# TEMPLATE_Circuit.net
KiCad netlist of a schematic drawn in Altium Designer
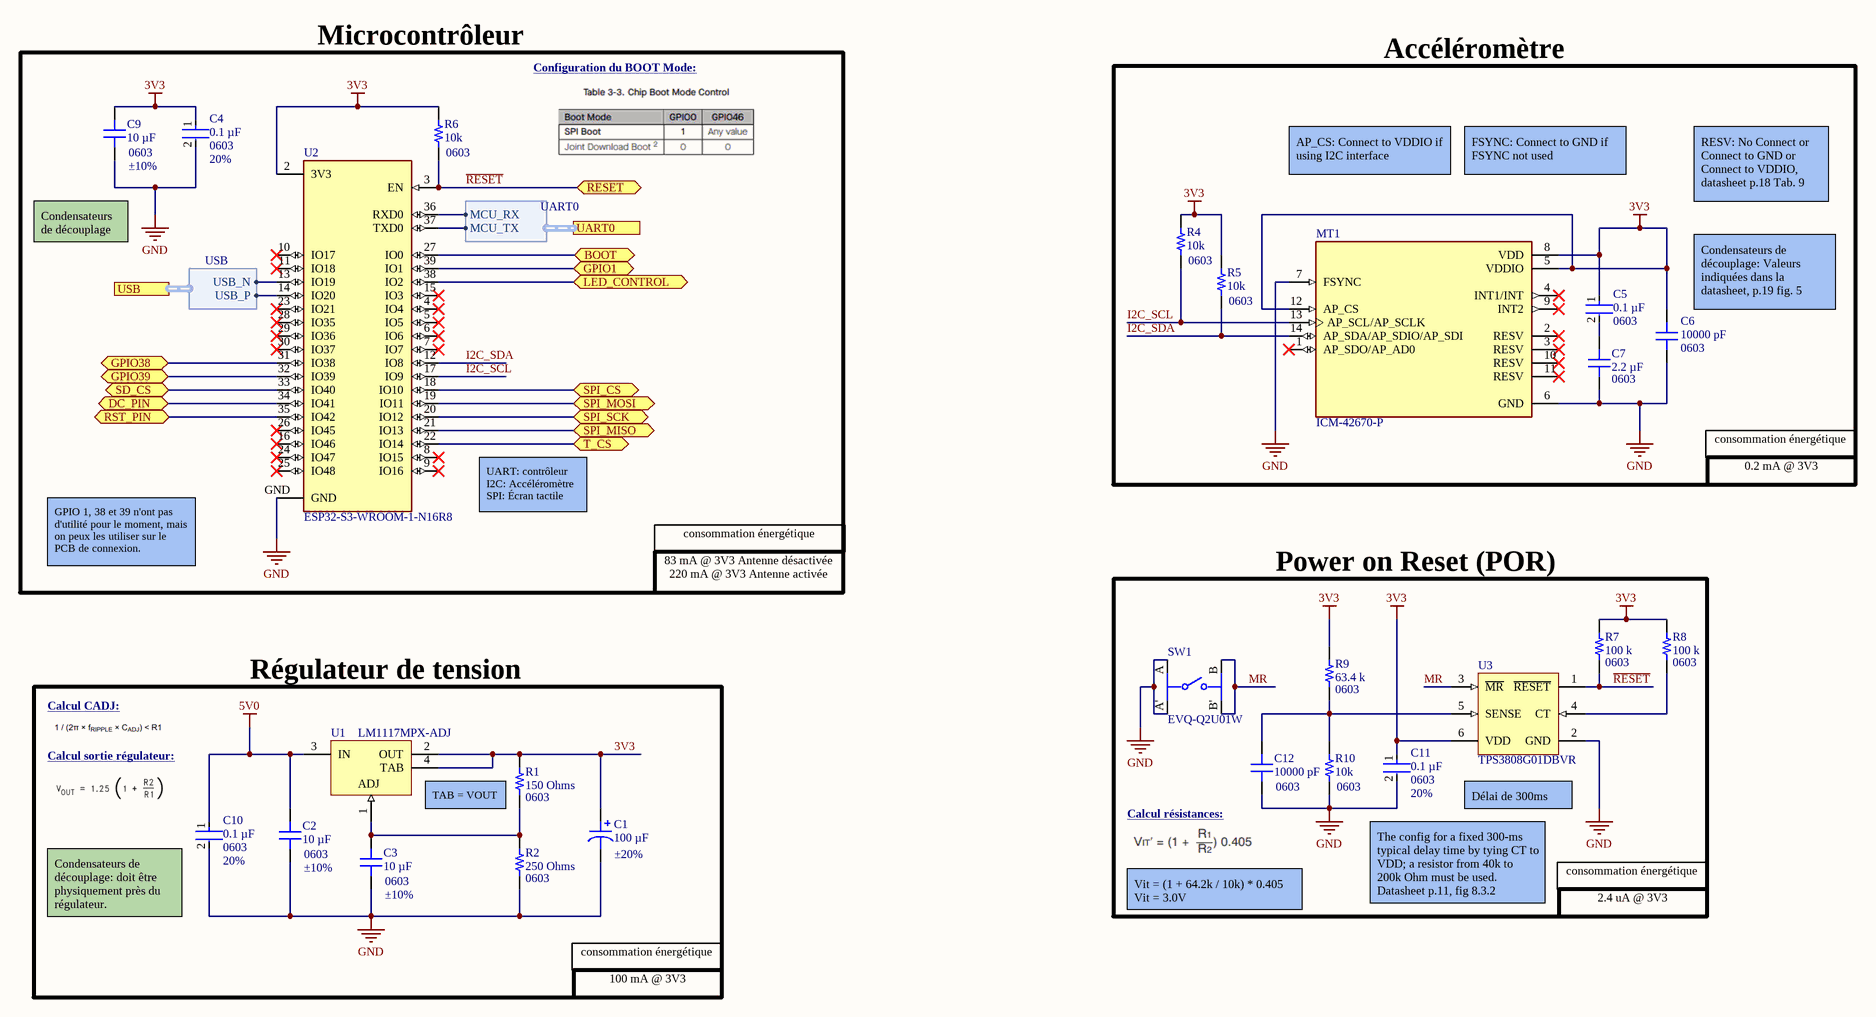
[diagram p0: TEMPLATE_Circuit.SchDoc]

(export (version "E")
  (design (tool "Eeschema 10.0.6"))
  (components
    (comp (ref "C1")
      (value "100 µF")
      (footprint "CAP ALSMD 6.6MM H6.1MM")
      (description "CAP ALUM 100UF 20% 10V SMD")
      (fields
        (field (name "PART NUMBER") "10SGV100M6.3X6.1")
        (field (name "MANUFACTURER") "Rubycon")
        (field (name "TOLERANCE") "±20%")
      )
      (libsource (lib "Celestial Altium Library - altium_library") (part "Polarised Capacitor"))
    )
    (comp (ref "C2")
      (value "10 µF")
      (footprint "CAP 0603_1608")
      (description "CAP CER 10UF 10V X5R 0603")
      (fields
        (field (name "PART NUMBER") "GRT188R61A106KE13D")
        (field (name "DEVICE PACKAGE") "0603")
        (field (name "MANUFACTURER") "Murata Electronics")
        (field (name "TOLERANCE") "±10%")
      )
      (libsource (lib "Celestial Altium Library - altium_library") (part "Capacitor"))
    )
    (comp (ref "C3")
      (value "10 µF")
      (footprint "CAP 0603_1608")
      (description "CAP CER 10UF 10V X5R 0603")
      (fields
        (field (name "PART NUMBER") "GRT188R61A106KE13D")
        (field (name "DEVICE PACKAGE") "0603")
        (field (name "MANUFACTURER") "Murata Electronics")
        (field (name "TOLERANCE") "±10%")
      )
      (libsource (lib "Celestial Altium Library - altium_library") (part "Capacitor"))
    )
    (comp (ref "C4")
      (value "0603ZC104MAT2A")
      (footprint "FP-0603-L_1_6_0_15-W_0_81-IPC_B")
      (description "General Purpose Ceramic Capacitor, 0603, 100nF, 20%, X7R, 15%, 10V")
      (fields
        (field (name "CASE CODE (IMPERIAL)") "0603")
        (field (name "TOLERANCE") "20%")
        (field (name "CAPACITANCE") "0.1 µF")
      )
      (libsource (lib "Altium Content Vault") (part "02cd4be3c70576c341d710602a673aa"))
    )
    (comp (ref "C5")
      (value "0603ZC104MAT2A")
      (footprint "FP-0603-L_1_6_0_15-W_0_81-IPC_B")
      (description "General Purpose Ceramic Capacitor, 0603, 100nF, 20%, X7R, 15%, 10V")
      (fields
        (field (name "CASE CODE (IMPERIAL)") "0603")
        (field (name "TOLERANCE") "20%")
        (field (name "CAPACITANCE") "0.1 µF")
      )
      (libsource (lib "Altium Content Vault") (part "02cd4be3c70576c341d710602a673aa"))
    )
    (comp (ref "C6")
      (value "10000 pF")
      (footprint "CAP 0603_1608")
      (description "CAP CER 0603 10NF 16V X7R 10%")
      (fields
        (field (name "PART NUMBER") "C0603C103K4RECAUTO")
        (field (name "MANUFACTURER") "KEMET")
        (field (name "PACKAGE / CASE") "0603")
      )
      (libsource (lib "Celestial Altium Library - altium_library") (part "Capacitor"))
    )
    (comp (ref "C7")
      (value "2.2 µF")
      (footprint "MURATA GRM188 0603_1608")
      (description "CAP CER 2.2UF 25V X5R 0603")
      (fields
        (field (name "PART NUMBER") "GRM188R61E225KA12D")
        (field (name "MANUFACTURER") "Murata Electronics")
        (field (name "PACKAGE / CASE") "0603")
      )
      (libsource (lib "Celestial Altium Library - altium_library") (part "Capacitor"))
    )
    (comp (ref "C9")
      (value "10 µF")
      (footprint "CAP 0603_1608")
      (description "CAP CER 10UF 10V X5R 0603")
      (fields
        (field (name "PART NUMBER") "GRT188R61A106KE13D")
        (field (name "DEVICE PACKAGE") "0603")
        (field (name "MANUFACTURER") "Murata Electronics")
        (field (name "TOLERANCE") "±10%")
      )
      (libsource (lib "Celestial Altium Library - altium_library") (part "Capacitor"))
    )
    (comp (ref "C10")
      (value "0603ZC104MAT2A")
      (footprint "FP-0603-L_1_6_0_15-W_0_81-IPC_B")
      (description "General Purpose Ceramic Capacitor, 0603, 100nF, 20%, X7R, 15%, 10V")
      (fields
        (field (name "CASE CODE (IMPERIAL)") "0603")
        (field (name "TOLERANCE") "20%")
        (field (name "CAPACITANCE") "0.1 µF")
      )
      (libsource (lib "Altium Content Vault") (part "02cd4be3c70576c341d710602a673aa"))
    )
    (comp (ref "C11")
      (value "0603ZC104MAT2A")
      (footprint "FP-0603-L_1_6_0_15-W_0_81-IPC_B")
      (description "General Purpose Ceramic Capacitor, 0603, 100nF, 20%, X7R, 15%, 10V")
      (fields
        (field (name "CASE CODE (IMPERIAL)") "0603")
        (field (name "TOLERANCE") "20%")
        (field (name "CAPACITANCE") "0.1 µF")
      )
      (libsource (lib "Altium Content Vault") (part "02cd4be3c70576c341d710602a673aa"))
    )
    (comp (ref "C12")
      (value "10000 pF")
      (footprint "CAP 0603_1608")
      (description "CAP CER 10000PF 100V X7R 0603")
      (fields
        (field (name "PART NUMBER") "AC0603KRX7R0BB103")
        (field (name "DEVICE PACKAGE") "0603")
        (field (name "MANUFACTURER") "Yageo")
      )
      (libsource (lib "Celestial Altium Library - altium_library") (part "Capacitor"))
    )
    (comp (ref "MT1")
      (value "ICM-42670-P")
      (footprint "XDCR_ICM-42670-P")
      (libsource (lib "ICM-42670-P") (part "ICM-42670-P"))
    )
    (comp (ref "R1")
      (value "150 Ohms")
      (footprint "RES 0603_1608")
      (description "RES 150 OHM 1% 1/10W 0603")
      (fields
        (field (name "PART NUMBER") "RMCF0603FT150R")
        (field (name "MANUFACTURER") "Stackpole Electronics Inc")
        (field (name "SUPPLIER DEVICE PACKAGE") "0603")
      )
      (libsource (lib "Celestial Altium Library - altium_library") (part "Resistor"))
    )
    (comp (ref "R2")
      (value "250 Ohms")
      (footprint "RES 0603_1608")
      (description "RES 250 OHM 5% 1/8W 0603")
      (fields
        (field (name "PART NUMBER") "CH0603-250RJNTA")
        (field (name "MANUFACTURER") "Vishay Sfernice")
        (field (name "SUPPLIER DEVICE PACKAGE") "0603")
      )
      (libsource (lib "Celestial Altium Library - altium_library") (part "Resistor"))
    )
    (comp (ref "R4")
      (value "10k")
      (footprint "RES 0603_1608")
      (description "RES 10K OHM 0.1% 1/16W 0603")
      (fields
        (field (name "PART NUMBER") "RNCS0603BKE10K0")
        (field (name "MANUFACTURER") "Stackpole Electronics Inc")
        (field (name "SUPPLIER DEVICE PACKAGE") "0603")
      )
      (libsource (lib "Celestial Altium Library - altium_library") (part "Resistor"))
    )
    (comp (ref "R5")
      (value "10k")
      (footprint "RES 0603_1608")
      (description "RES 10K OHM 0.1% 1/16W 0603")
      (fields
        (field (name "PART NUMBER") "RNCS0603BKE10K0")
        (field (name "MANUFACTURER") "Stackpole Electronics Inc")
        (field (name "SUPPLIER DEVICE PACKAGE") "0603")
      )
      (libsource (lib "Celestial Altium Library - altium_library") (part "Resistor"))
    )
    (comp (ref "R6")
      (value "10k")
      (footprint "RES 0603_1608")
      (description "RES 10K OHM 0.1% 1/16W 0603")
      (fields
        (field (name "PART NUMBER") "RNCS0603BKE10K0")
        (field (name "MANUFACTURER") "Stackpole Electronics Inc")
        (field (name "SUPPLIER DEVICE PACKAGE") "0603")
      )
      (libsource (lib "Celestial Altium Library - altium_library") (part "Resistor"))
    )
    (comp (ref "R7")
      (value "100 k")
      (footprint "RES 0603_1608")
      (description "RES SMD 100K OHM 1% 1/4W 0603")
      (fields
        (field (name "PART NUMBER") "RCS0603100KFKEA")
        (field (name "MANUFACTURER") "Vishay Dale")
        (field (name "SUPPLIER DEVICE PACKAGE") "0603")
      )
      (libsource (lib "Celestial Altium Library - altium_library") (part "Resistor"))
    )
    (comp (ref "R8")
      (value "100 k")
      (footprint "RES 0603_1608")
      (description "RES SMD 100K OHM 1% 1/4W 0603")
      (fields
        (field (name "PART NUMBER") "RCS0603100KFKEA")
        (field (name "MANUFACTURER") "Vishay Dale")
        (field (name "SUPPLIER DEVICE PACKAGE") "0603")
      )
      (libsource (lib "Celestial Altium Library - altium_library") (part "Resistor"))
    )
    (comp (ref "R9")
      (value "63.4 k")
      (footprint "YAGEO RES 0603_1608")
      (description "RES 63.4K OHM 1% 1/10W 0603")
      (fields
        (field (name "PART NUMBER") "RC0603FR-0763K4L")
        (field (name "MANUFACTURER") "Yageo")
        (field (name "PACKAGE / CASE") "0603")
      )
      (libsource (lib "Celestial Altium Library - altium_library") (part "Resistor"))
    )
    (comp (ref "R10")
      (value "10k")
      (footprint "RES 0603_1608")
      (description "RES 10K OHM 0.1% 1/16W 0603")
      (fields
        (field (name "PART NUMBER") "RNCS0603BKE10K0")
        (field (name "MANUFACTURER") "Stackpole Electronics Inc")
        (field (name "SUPPLIER DEVICE PACKAGE") "0603")
      )
      (libsource (lib "Celestial Altium Library - altium_library") (part "Resistor"))
    )
    (comp (ref "SW1")
      (value "EVQ-Q2U01W")
      (footprint "FP-EVQ-Q2U01W-MFG")
      (description "SWITCH TACTILE SPST-NO 0.02A 15V")
      (libsource (lib "Altium Content Vault") (part "9677229990528492022b31d4503349f"))
    )
    (comp (ref "U1")
      (value "LM1117MPX-ADJ")
      (footprint "MP04A_N")
      (description "800mA Low-Dropout Linear Regulator, 4-pin SOT-223")
      (fields (field (name "MANUFACTURER") "National Semiconductor"))
      (libsource (lib "Altium Content Vault") (part "PM-REG-LM1086ADJ-SOT4"))
    )
    (comp (ref "U2")
      (value "ESP32-S3-WROOM-1-N16R8")
      (footprint "XCVR_ESP32-S3-WROOM-1-N16R2")
      (description "Bluetooth, WiFi 802.11b/g/n, Bluetooth v5.0 Transceiver Module 2.4GHz PCB Trace Surface Mount")
      (fields (field (name "MF") "Espressif Systems") (field (name "MP") "ESP32S3WROOM1N16R2"))
      (libsource (lib "Cegep de Sherbrooke") (part "ESP32-S3-WROOM-1-N16R2"))
    )
    (comp (ref "U3")
      (value "TPS3808G01DBVR")
      (footprint "DBV0006A_L")
      (fields (field (name "MANUFACTURER") "Texas Instruments"))
      (libsource (lib "Altium Content Vault") (part "TI-TPS3808G01DBV6"))
    )
  )
  (nets
    (net (code "3") (name "/BOOT") (class "Default")
      (node (ref "U2") (pin "27") (pinfunction "IO0_27") (pintype "bidirectional"))
    )
    (net (code "4") (name "/DC_PIN") (class "Default")
      (node (ref "U2") (pin "34") (pinfunction "IO41_34") (pintype "bidirectional"))
    )
    (net (code "5") (name "/GPIO1") (class "Default")
      (node (ref "U2") (pin "39") (pinfunction "IO1_39") (pintype "bidirectional"))
    )
    (net (code "6") (name "/GPIO38") (class "Default")
      (node (ref "U2") (pin "31") (pinfunction "IO38_31") (pintype "bidirectional"))
    )
    (net (code "7") (name "/GPIO39") (class "Default")
      (node (ref "U2") (pin "32") (pinfunction "IO39_32") (pintype "bidirectional"))
    )
    (net (code "8") (name "/I2C_SCL") (class "Default")
      (node (ref "MT1") (pin "13") (pinfunction "AP_SCL/AP_SCLK_13") (pintype "input"))
      (node (ref "R4") (pin "1") (pinfunction "1_1") (pintype "passive"))
      (node (ref "U2") (pin "17") (pinfunction "IO9_17") (pintype "bidirectional"))
    )
    (net (code "9") (name "/I2C_SDA") (class "Default")
      (node (ref "MT1") (pin "14") (pinfunction "AP_SDA/AP_SDIO/AP_SDI_14") (pintype "bidirectional"))
      (node (ref "R5") (pin "1") (pinfunction "1_1") (pintype "passive"))
      (node (ref "U2") (pin "12") (pinfunction "IO8_12") (pintype "bidirectional"))
    )
    (net (code "10") (name "/LED_CONTROL") (class "Default")
      (node (ref "U2") (pin "38") (pinfunction "IO2_38") (pintype "bidirectional"))
    )
    (net (code "11") (name "/MCU_RX") (class "Default")
      (node (ref "U2") (pin "36") (pinfunction "RXD0_36") (pintype "bidirectional"))
    )
    (net (code "12") (name "/MCU_TX") (class "Default")
      (node (ref "U2") (pin "37") (pinfunction "TXD0_37") (pintype "bidirectional"))
    )
    (net (code "13") (name "/MR") (class "Default")
      (node (ref "SW1") (pin "B") (pinfunction "B_B") (pintype "passive"))
      (node (ref "SW1") (pin "B'") (pinfunction "B'_B'") (pintype "passive"))
      (node (ref "U3") (pin "3") (pinfunction "~{MR}_3") (pintype "input"))
    )
    (net (code "14") (name "/RESET") (class "Default")
      (node (ref "R6") (pin "1") (pinfunction "1_1") (pintype "passive"))
      (node (ref "R7") (pin "1") (pinfunction "1_1") (pintype "passive"))
      (node (ref "U2") (pin "3") (pinfunction "EN_3") (pintype "input"))
      (node (ref "U3") (pin "1") (pinfunction "~{RESET}_1") (pintype "tri_state"))
    )
    (net (code "15") (name "/RST_PIN") (class "Default")
      (node (ref "U2") (pin "35") (pinfunction "IO42_35") (pintype "bidirectional"))
    )
    (net (code "16") (name "/SD_CS") (class "Default")
      (node (ref "U2") (pin "33") (pinfunction "IO40_33") (pintype "bidirectional"))
    )
    (net (code "17") (name "/SPI_CS") (class "Default")
      (node (ref "U2") (pin "18") (pinfunction "IO10_18") (pintype "bidirectional"))
    )
    (net (code "18") (name "/SPI_MISO") (class "Default")
      (node (ref "U2") (pin "21") (pinfunction "IO13_21") (pintype "bidirectional"))
    )
    (net (code "19") (name "/SPI_MOSI") (class "Default")
      (node (ref "U2") (pin "19") (pinfunction "IO11_19") (pintype "bidirectional"))
    )
    (net (code "20") (name "/SPI_SCK") (class "Default")
      (node (ref "U2") (pin "20") (pinfunction "IO12_20") (pintype "bidirectional"))
    )
    (net (code "21") (name "/T_CS") (class "Default")
      (node (ref "U2") (pin "22") (pinfunction "IO14_22") (pintype "bidirectional"))
    )
    (net (code "22") (name "/USB_N") (class "Default")
      (node (ref "U2") (pin "13") (pinfunction "IO19_13") (pintype "bidirectional"))
    )
    (net (code "23") (name "/USB_P") (class "Default")
      (node (ref "U2") (pin "14") (pinfunction "IO20_14") (pintype "bidirectional"))
    )
    (net (code "26") (name "3V3") (class "Default")
      (node (ref "C1") (pin "1") (pinfunction "1_1") (pintype "passive"))
      (node (ref "C11") (pin "1") (pinfunction "1_1") (pintype "passive"))
      (node (ref "C4") (pin "1") (pinfunction "1_1") (pintype "passive"))
      (node (ref "C5") (pin "1") (pinfunction "1_1") (pintype "passive"))
      (node (ref "C6") (pin "2") (pinfunction "2_2") (pintype "passive"))
      (node (ref "C9") (pin "2") (pinfunction "2_2") (pintype "passive"))
      (node (ref "MT1") (pin "12") (pinfunction "AP_CS_12") (pintype "input"))
      (node (ref "MT1") (pin "5") (pinfunction "VDDIO_5") (pintype "power_in"))
      (node (ref "MT1") (pin "8") (pinfunction "VDD_8") (pintype "power_in"))
      (node (ref "R1") (pin "2") (pinfunction "2_2") (pintype "passive"))
      (node (ref "R4") (pin "2") (pinfunction "2_2") (pintype "passive"))
      (node (ref "R5") (pin "2") (pinfunction "2_2") (pintype "passive"))
      (node (ref "R6") (pin "2") (pinfunction "2_2") (pintype "passive"))
      (node (ref "R7") (pin "2") (pinfunction "2_2") (pintype "passive"))
      (node (ref "R8") (pin "2") (pinfunction "2_2") (pintype "passive"))
      (node (ref "R9") (pin "2") (pinfunction "2_2") (pintype "passive"))
      (node (ref "U1") (pin "2") (pinfunction "OUT_2") (pintype "power_in"))
      (node (ref "U1") (pin "4") (pinfunction "TAB_4") (pintype "power_in"))
      (node (ref "U2") (pin "2") (pinfunction "3V3_2") (pintype "power_in"))
      (node (ref "U3") (pin "6") (pinfunction "VDD_6") (pintype "power_in"))
    )
    (net (code "27") (name "5V0") (class "Default")
      (node (ref "C10") (pin "1") (pinfunction "1_1") (pintype "passive"))
      (node (ref "C2") (pin "2") (pinfunction "2_2") (pintype "passive"))
      (node (ref "U1") (pin "3") (pinfunction "IN_3") (pintype "power_in"))
    )
    (net (code "28") (name "GND") (class "Default")
      (node (ref "C1") (pin "2") (pinfunction "2_2") (pintype "passive"))
      (node (ref "C10") (pin "2") (pinfunction "2_2") (pintype "passive"))
      (node (ref "C11") (pin "2") (pinfunction "2_2") (pintype "passive"))
      (node (ref "C12") (pin "1") (pinfunction "1_1") (pintype "passive"))
      (node (ref "C2") (pin "1") (pinfunction "1_1") (pintype "passive"))
      (node (ref "C3") (pin "1") (pinfunction "1_1") (pintype "passive"))
      (node (ref "C4") (pin "2") (pinfunction "2_2") (pintype "passive"))
      (node (ref "C6") (pin "1") (pinfunction "1_1") (pintype "passive"))
      (node (ref "C7") (pin "1") (pinfunction "1_1") (pintype "passive"))
      (node (ref "C9") (pin "1") (pinfunction "1_1") (pintype "passive"))
      (node (ref "MT1") (pin "6") (pinfunction "GND_6") (pintype "power_in"))
      (node (ref "MT1") (pin "7") (pinfunction "FSYNC_7") (pintype "input"))
      (node (ref "R10") (pin "1") (pinfunction "1_1") (pintype "passive"))
      (node (ref "R2") (pin "1") (pinfunction "1_1") (pintype "passive"))
      (node (ref "SW1") (pin "A") (pinfunction "A_A") (pintype "passive"))
      (node (ref "SW1") (pin "A'") (pinfunction "A'_A'") (pintype "passive"))
      (node (ref "U2") (pin "GND") (pinfunction "GND_GND") (pintype "power_in"))
      (node (ref "U3") (pin "2") (pinfunction "GND_2") (pintype "power_in"))
    )
    (net (code "29") (name "Net-(C5-Pad2)") (class "Default")
      (node (ref "C5") (pin "2") (pinfunction "2_2") (pintype "passive"))
      (node (ref "C7") (pin "2") (pinfunction "2_2") (pintype "passive"))
    )
    (net (code "30") (name "Net-(U1-ADJ)") (class "Default")
      (node (ref "C3") (pin "2") (pinfunction "2_2") (pintype "passive"))
      (node (ref "R1") (pin "1") (pinfunction "1_1") (pintype "passive"))
      (node (ref "R2") (pin "2") (pinfunction "2_2") (pintype "passive"))
      (node (ref "U1") (pin "1") (pinfunction "ADJ_1") (pintype "input"))
    )
    (net (code "31") (name "Net-(U3-CT)") (class "Default")
      (node (ref "R8") (pin "1") (pinfunction "1_1") (pintype "passive"))
      (node (ref "U3") (pin "4") (pinfunction "CT_4") (pintype "input"))
    )
    (net (code "32") (name "Net-(U3-SENSE)") (class "Default")
      (node (ref "C12") (pin "2") (pinfunction "2_2") (pintype "passive"))
      (node (ref "R10") (pin "2") (pinfunction "2_2") (pintype "passive"))
      (node (ref "R9") (pin "1") (pinfunction "1_1") (pintype "passive"))
      (node (ref "U3") (pin "5") (pinfunction "SENSE_5") (pintype "input"))
    )
    (net (code "33") (name "unconnected-(MT1-AP_SDO{slash}AP_AD0-Pad1)") (class "Default")
      (node (ref "MT1") (pin "1") (pinfunction "AP_SDO/AP_AD0_1") (pintype "bidirectional+no_connect"))
    )
    (net (code "34") (name "unconnected-(MT1-INT1{slash}INT-Pad4)") (class "Default")
      (node (ref "MT1") (pin "4") (pinfunction "INT1/INT_4") (pintype "output+no_connect"))
    )
    (net (code "35") (name "unconnected-(MT1-INT2-Pad9)") (class "Default")
      (node (ref "MT1") (pin "9") (pinfunction "INT2_9") (pintype "output+no_connect"))
    )
    (net (code "36") (name "unconnected-(MT1-RESV-Pad2)") (class "Default")
      (node (ref "MT1") (pin "2") (pinfunction "RESV_2") (pintype "passive+no_connect"))
    )
    (net (code "37") (name "unconnected-(MT1-RESV-Pad3)") (class "Default")
      (node (ref "MT1") (pin "3") (pinfunction "RESV_3") (pintype "passive+no_connect"))
    )
    (net (code "38") (name "unconnected-(MT1-RESV-Pad10)") (class "Default")
      (node (ref "MT1") (pin "10") (pinfunction "RESV_10") (pintype "passive+no_connect"))
    )
    (net (code "39") (name "unconnected-(MT1-RESV-Pad11)") (class "Default")
      (node (ref "MT1") (pin "11") (pinfunction "RESV_11") (pintype "passive+no_connect"))
    )
    (net (code "40") (name "unconnected-(U2-IO3-Pad15)") (class "Default")
      (node (ref "U2") (pin "15") (pinfunction "IO3_15") (pintype "bidirectional+no_connect"))
    )
    (net (code "41") (name "unconnected-(U2-IO4-Pad4)") (class "Default")
      (node (ref "U2") (pin "4") (pinfunction "IO4_4") (pintype "bidirectional+no_connect"))
    )
    (net (code "42") (name "unconnected-(U2-IO5-Pad5)") (class "Default")
      (node (ref "U2") (pin "5") (pinfunction "IO5_5") (pintype "bidirectional+no_connect"))
    )
    (net (code "43") (name "unconnected-(U2-IO6-Pad6)") (class "Default")
      (node (ref "U2") (pin "6") (pinfunction "IO6_6") (pintype "bidirectional+no_connect"))
    )
    (net (code "44") (name "unconnected-(U2-IO7-Pad7)") (class "Default")
      (node (ref "U2") (pin "7") (pinfunction "IO7_7") (pintype "bidirectional+no_connect"))
    )
    (net (code "45") (name "unconnected-(U2-IO15-Pad8)") (class "Default")
      (node (ref "U2") (pin "8") (pinfunction "IO15_8") (pintype "bidirectional+no_connect"))
    )
    (net (code "46") (name "unconnected-(U2-IO16-Pad9)") (class "Default")
      (node (ref "U2") (pin "9") (pinfunction "IO16_9") (pintype "bidirectional+no_connect"))
    )
    (net (code "47") (name "unconnected-(U2-IO17-Pad10)") (class "Default")
      (node (ref "U2") (pin "10") (pinfunction "IO17_10") (pintype "bidirectional+no_connect"))
    )
    (net (code "48") (name "unconnected-(U2-IO18-Pad11)") (class "Default")
      (node (ref "U2") (pin "11") (pinfunction "IO18_11") (pintype "bidirectional+no_connect"))
    )
    (net (code "49") (name "unconnected-(U2-IO21-Pad23)") (class "Default")
      (node (ref "U2") (pin "23") (pinfunction "IO21_23") (pintype "bidirectional+no_connect"))
    )
    (net (code "50") (name "unconnected-(U2-IO35-Pad28)") (class "Default")
      (node (ref "U2") (pin "28") (pinfunction "IO35_28") (pintype "bidirectional+no_connect"))
    )
    (net (code "51") (name "unconnected-(U2-IO36-Pad29)") (class "Default")
      (node (ref "U2") (pin "29") (pinfunction "IO36_29") (pintype "bidirectional+no_connect"))
    )
    (net (code "52") (name "unconnected-(U2-IO37-Pad30)") (class "Default")
      (node (ref "U2") (pin "30") (pinfunction "IO37_30") (pintype "bidirectional+no_connect"))
    )
    (net (code "53") (name "unconnected-(U2-IO45-Pad26)") (class "Default")
      (node (ref "U2") (pin "26") (pinfunction "IO45_26") (pintype "bidirectional+no_connect"))
    )
    (net (code "54") (name "unconnected-(U2-IO46-Pad16)") (class "Default")
      (node (ref "U2") (pin "16") (pinfunction "IO46_16") (pintype "bidirectional+no_connect"))
    )
    (net (code "55") (name "unconnected-(U2-IO47-Pad24)") (class "Default")
      (node (ref "U2") (pin "24") (pinfunction "IO47_24") (pintype "bidirectional+no_connect"))
    )
    (net (code "56") (name "unconnected-(U2-IO48-Pad25)") (class "Default")
      (node (ref "U2") (pin "25") (pinfunction "IO48_25") (pintype "bidirectional+no_connect"))
    )
  )
)
